# DM1098LUXD-LITE_IMX214.net
KiCad netlist of a schematic drawn in Altium Designer
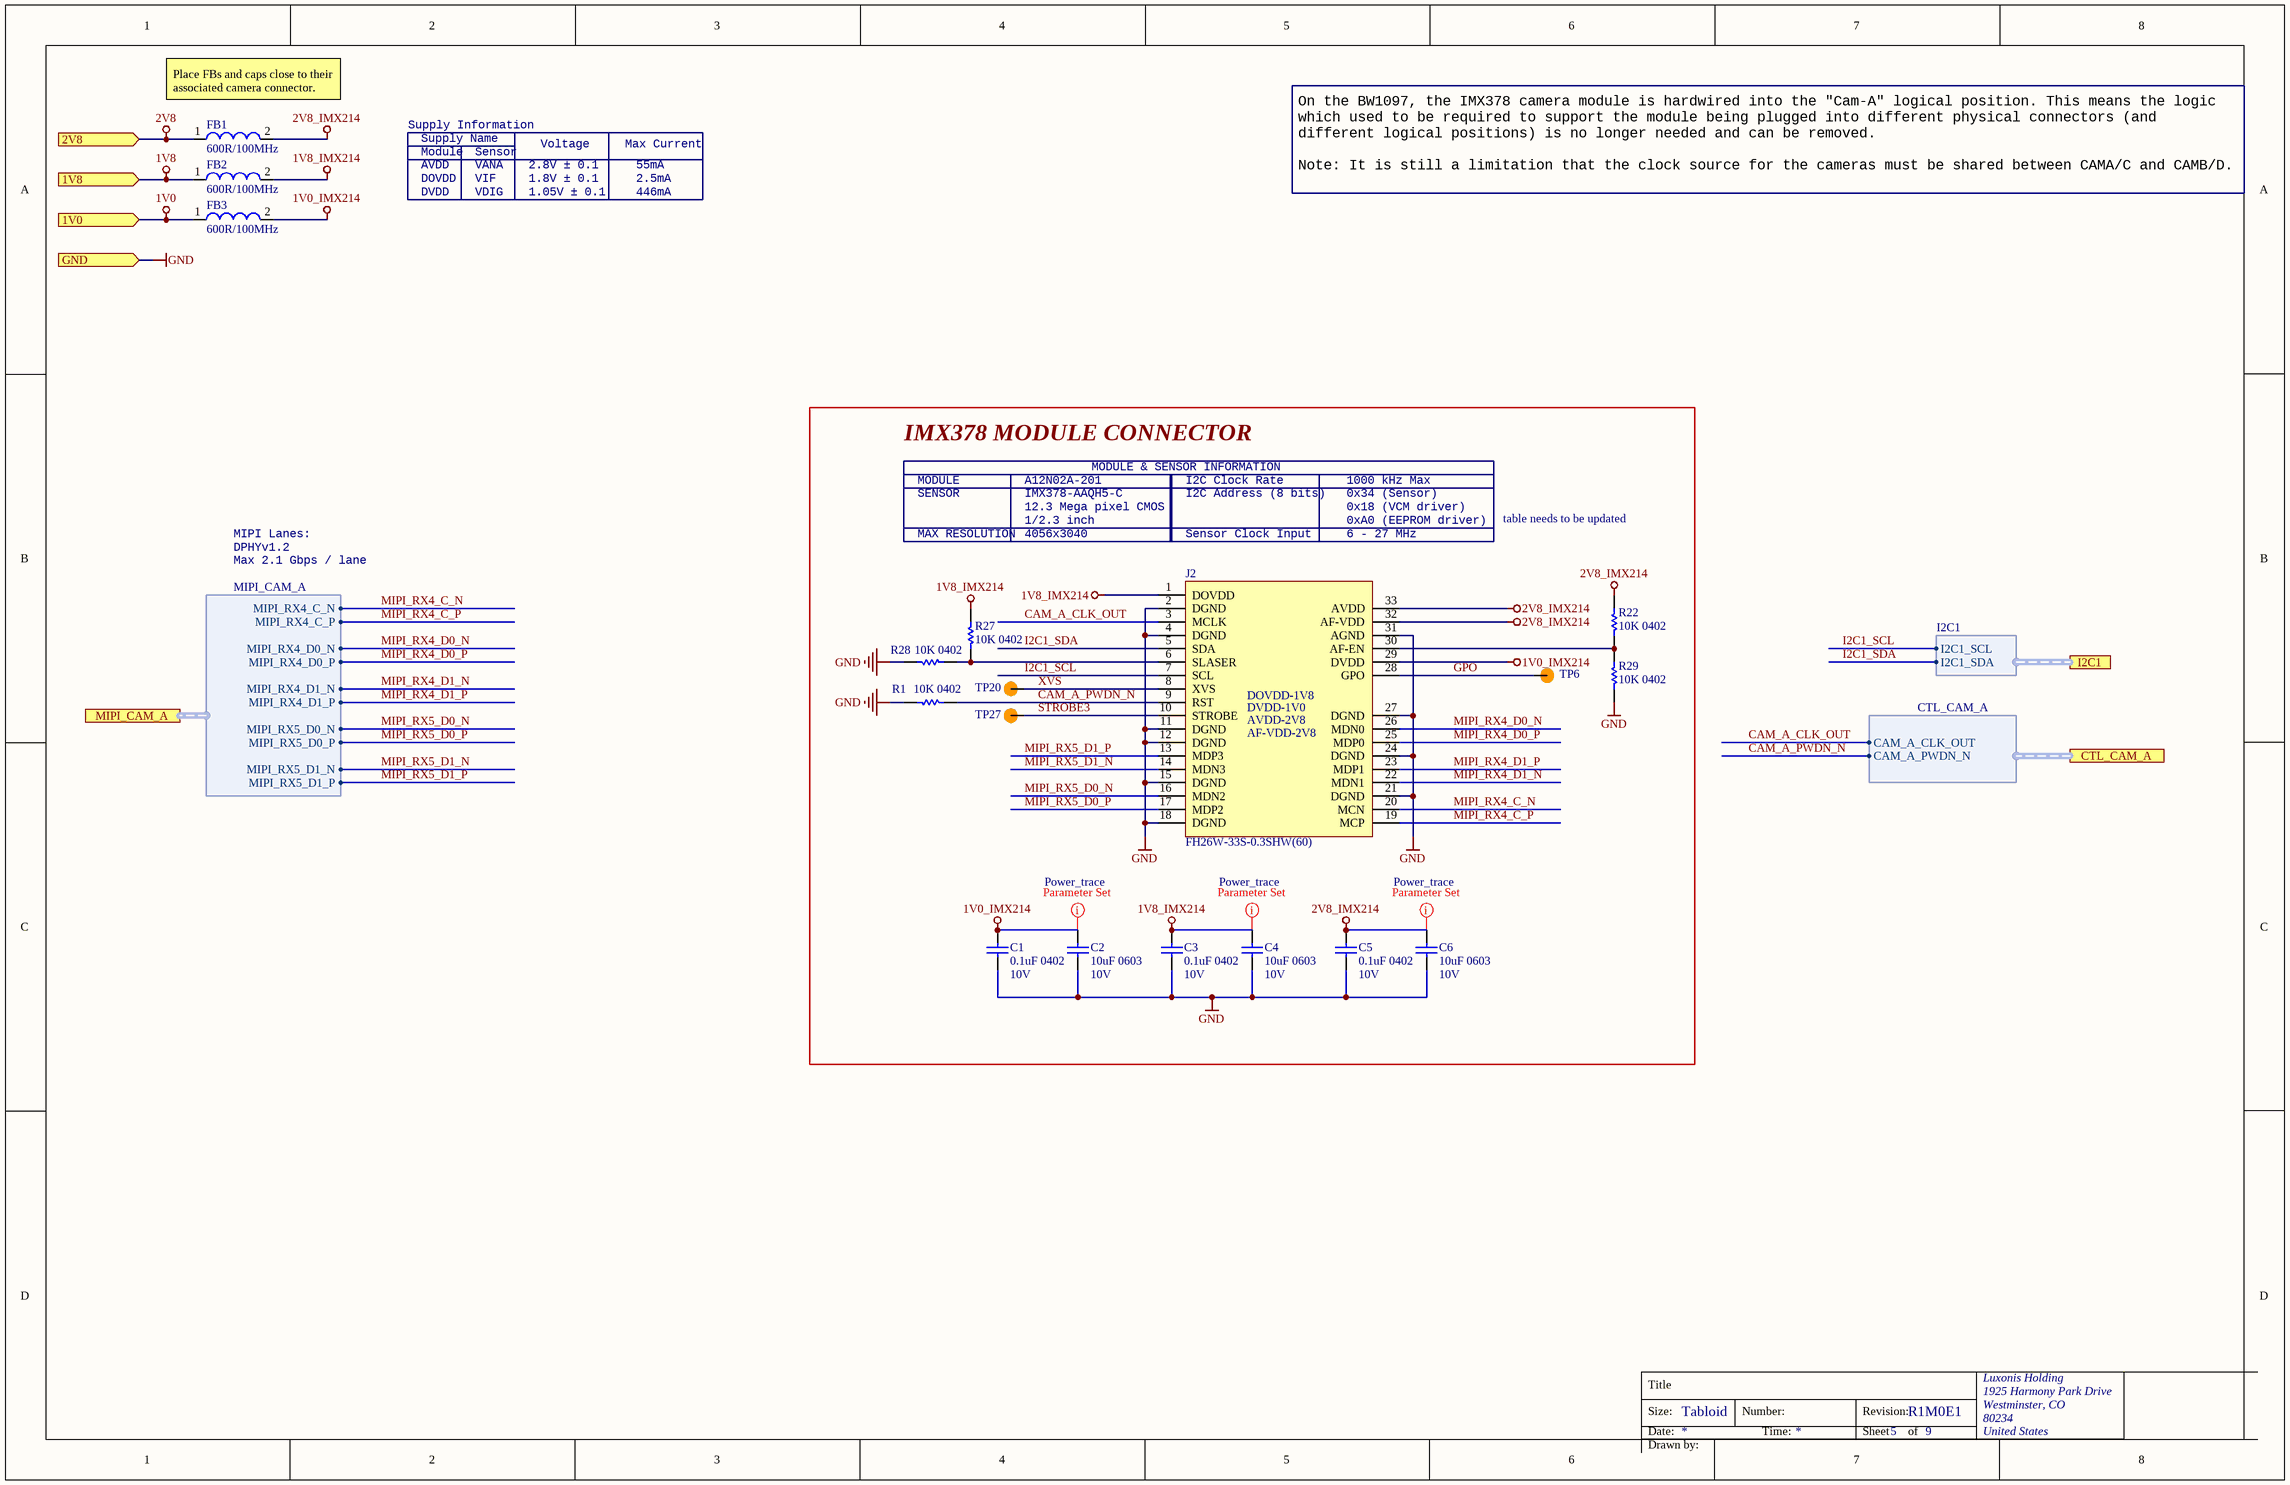
[diagram p0: DM1098LUXD-LITE_IMX214.SchDoc]

(export (version "E")
  (design (tool "Eeschema 10.0.6"))
  (components
    (comp (ref "C1")
      (value "0.1uF 0402")
      (footprint "CAP_Altium_Vault_Generic:CAPC0402(1005)70_L")
      (description "CAP CER 0.1UF 10V X7R 0402 5%")
      (fields (field (name "TOLERANCE") "5%") (field (name "VOLTAGE RATING") "10V"))
      (libsource (lib "LuxonisMaster") (part "GRM155R71A104JA01D"))
    )
    (comp (ref "C2")
      (value "10uF 0603")
      (footprint "CAP_Altium_Vault_Generic:CAPC0603(1608)100_L")
      (description "CAP CER 10UF 10V X5R 0603 20%")
      (fields (field (name "TOLERANCE") "20%") (field (name "VOLTAGE RATING") "10V"))
      (libsource (lib "LuxonisMaster") (part "GRM188R61A106ME69D"))
    )
    (comp (ref "C3")
      (value "0.1uF 0402")
      (footprint "CAP_Altium_Vault_Generic:CAPC0402(1005)70_L")
      (description "CAP CER 0.1UF 10V X7R 0402 5%")
      (fields (field (name "TOLERANCE") "5%") (field (name "VOLTAGE RATING") "10V"))
      (libsource (lib "LuxonisMaster") (part "GRM155R71A104JA01D"))
    )
    (comp (ref "C4")
      (value "10uF 0603")
      (footprint "CAP_Altium_Vault_Generic:CAPC0603(1608)100_L")
      (description "CAP CER 10UF 10V X5R 0603 20%")
      (fields (field (name "TOLERANCE") "20%") (field (name "VOLTAGE RATING") "10V"))
      (libsource (lib "LuxonisMaster") (part "GRM188R61A106ME69D"))
    )
    (comp (ref "C5")
      (value "0.1uF 0402")
      (footprint "CAP_Altium_Vault_Generic:CAPC0402(1005)70_L")
      (description "CAP CER 0.1UF 10V X7R 0402 5%")
      (fields (field (name "TOLERANCE") "5%") (field (name "VOLTAGE RATING") "10V"))
      (libsource (lib "LuxonisMaster") (part "GRM155R71A104JA01D"))
    )
    (comp (ref "C6")
      (value "10uF 0603")
      (footprint "CAP_Altium_Vault_Generic:CAPC0603(1608)100_L")
      (description "CAP CER 10UF 10V X5R 0603 20%")
      (fields (field (name "TOLERANCE") "20%") (field (name "VOLTAGE RATING") "10V"))
      (libsource (lib "LuxonisMaster") (part "GRM188R61A106ME69D"))
    )
    (comp (ref "FB1")
      (value "600R/100MHz")
      (footprint "LuxonisMaster:2508056017Y2")
      (description "FERRITE BEAD, 0.1OHM, 2A, 0805, 600R/100MHz")
      (fields (field (name "TOLERANCE") "25%"))
      (libsource (lib "LuxonisMaster") (part "2508056017Y2"))
    )
    (comp (ref "FB2")
      (value "600R/100MHz")
      (footprint "LuxonisMaster:2508056017Y2")
      (description "FERRITE BEAD, 0.1OHM, 2A, 0805, 600R/100MHz")
      (fields (field (name "TOLERANCE") "25%"))
      (libsource (lib "LuxonisMaster") (part "2508056017Y2"))
    )
    (comp (ref "FB3")
      (value "600R/100MHz")
      (footprint "LuxonisMaster:2508056017Y2")
      (description "FERRITE BEAD, 0.1OHM, 2A, 0805, 600R/100MHz")
      (fields (field (name "TOLERANCE") "25%"))
      (libsource (lib "LuxonisMaster") (part "2508056017Y2"))
    )
    (comp (ref "J2")
      (value "FH26W-33S-0.3SHW(60)")
      (footprint "ACIMX-214")
      (description "FFC/FPC Connector, 33 Contact(s), 1 Row(s), Female, Right Angle, Surface Mount Terminal")
      (libsource (lib "DM1098LUXD-LITE") (part "AC-IMX214_Connector"))
    )
    (comp (ref "R1")
      (value "10K 0402")
      (footprint "RES_Altium_Vault_Generic:RESC0402(1005)_L")
      (fields (field (name "TOLERANCE") "1%"))
      (libsource (lib "LuxonisMaster") (part "RC0402FR-1310KL"))
    )
    (comp (ref "R22")
      (value "10K 0402")
      (footprint "RES_Altium_Vault_Generic:RESC0402(1005)_L")
      (fields (field (name "TOLERANCE") "1%"))
      (libsource (lib "LuxonisMaster") (part "RC0402FR-1310KL"))
    )
    (comp (ref "R27")
      (value "10K 0402")
      (footprint "RES_Altium_Vault_Generic:RESC0402(1005)_L")
      (fields (field (name "TOLERANCE") "1%"))
      (libsource (lib "LuxonisMaster") (part "RC0402FR-1310KL"))
    )
    (comp (ref "R28")
      (value "10K 0402")
      (footprint "RES_Altium_Vault_Generic:RESC0402(1005)_L")
      (fields (field (name "TOLERANCE") "1%"))
      (libsource (lib "LuxonisMaster") (part "RC0402FR-1310KL"))
    )
    (comp (ref "R29")
      (value "10K 0402")
      (footprint "RES_Altium_Vault_Generic:RESC0402(1005)_L")
      (fields (field (name "TOLERANCE") "1%"))
      (libsource (lib "LuxonisMaster") (part "RC0402FR-1310KL"))
    )
    (comp (ref "TP6")
      (value "TP100_200_NS")
      (footprint "LuxonisMaster:TP100_200_NS")
      (libsource (lib "LuxonisMaster") (part "TEST_POINT"))
    )
    (comp (ref "TP20")
      (value "TP100_200_NS")
      (footprint "LuxonisMaster:TP100_200_NS")
      (libsource (lib "LuxonisMaster") (part "TEST_POINT"))
    )
    (comp (ref "TP27")
      (value "TP100_200_NS")
      (footprint "LuxonisMaster:TP100_200_NS")
      (libsource (lib "LuxonisMaster") (part "TEST_POINT"))
    )
  )
  (nets
    (net (code "4") (name "/CAM_A_CLK_OUT") (class "Default")
      (node (ref "J2") (pin "3") (pinfunction "MCLK_3") (pintype "passive"))
    )
    (net (code "5") (name "/CAM_A_PWDN_N") (class "Default")
      (node (ref "J2") (pin "9") (pinfunction "RST_9") (pintype "passive"))
      (node (ref "R1") (pin "1") (pinfunction "1_1") (pintype "passive"))
    )
    (net (code "6") (name "/GPO") (class "Default")
      (node (ref "J2") (pin "28") (pinfunction "GPO_28") (pintype "passive"))
      (node (ref "TP6") (pin "1") (pintype "passive"))
    )
    (net (code "7") (name "/I2C1_SCL") (class "Default")
      (node (ref "J2") (pin "7") (pinfunction "SCL_7") (pintype "passive"))
    )
    (net (code "8") (name "/I2C1_SDA") (class "Default")
      (node (ref "J2") (pin "5") (pinfunction "SDA_5") (pintype "passive"))
    )
    (net (code "9") (name "/MIPI_RX4_C_N") (class "Default")
      (node (ref "J2") (pin "20") (pinfunction "MCN_20") (pintype "passive"))
    )
    (net (code "10") (name "/MIPI_RX4_C_P") (class "Default")
      (node (ref "J2") (pin "19") (pinfunction "MCP_19") (pintype "passive"))
    )
    (net (code "11") (name "/MIPI_RX4_D0_N") (class "Default")
      (node (ref "J2") (pin "26") (pinfunction "MDN0_26") (pintype "passive"))
    )
    (net (code "12") (name "/MIPI_RX4_D0_P") (class "Default")
      (node (ref "J2") (pin "25") (pinfunction "MDP0_25") (pintype "passive"))
    )
    (net (code "13") (name "/MIPI_RX4_D1_N") (class "Default")
      (node (ref "J2") (pin "22") (pinfunction "MDN1_22") (pintype "passive"))
    )
    (net (code "14") (name "/MIPI_RX4_D1_P") (class "Default")
      (node (ref "J2") (pin "23") (pinfunction "MDP1_23") (pintype "passive"))
    )
    (net (code "15") (name "/MIPI_RX5_D0_N") (class "Default")
      (node (ref "J2") (pin "16") (pinfunction "MDN2_16") (pintype "passive"))
    )
    (net (code "16") (name "/MIPI_RX5_D0_P") (class "Default")
      (node (ref "J2") (pin "17") (pinfunction "MDP2_17") (pintype "passive"))
    )
    (net (code "17") (name "/MIPI_RX5_D1_N") (class "Default")
      (node (ref "J2") (pin "14") (pinfunction "MDN3_14") (pintype "passive"))
    )
    (net (code "18") (name "/MIPI_RX5_D1_P") (class "Default")
      (node (ref "J2") (pin "13") (pinfunction "MDP3_13") (pintype "passive"))
    )
    (net (code "19") (name "/STROBE3") (class "Default")
      (node (ref "J2") (pin "10") (pinfunction "STROBE_10") (pintype "passive"))
      (node (ref "TP27") (pin "1") (pintype "passive"))
    )
    (net (code "20") (name "/XVS") (class "Default")
      (node (ref "J2") (pin "8") (pinfunction "XVS_8") (pintype "passive"))
      (node (ref "TP20") (pin "1") (pintype "passive"))
    )
    (net (code "24") (name "1V0") (class "Default")
      (node (ref "FB3") (pin "1") (pinfunction "1_1") (pintype "passive"))
    )
    (net (code "25") (name "1V0_IMX214") (class "Default")
      (node (ref "C1") (pin "2") (pinfunction "2_2") (pintype "passive"))
      (node (ref "C2") (pin "2") (pinfunction "2_2") (pintype "passive"))
      (node (ref "FB3") (pin "2") (pinfunction "2_2") (pintype "passive"))
      (node (ref "J2") (pin "29") (pinfunction "DVDD_29") (pintype "passive"))
    )
    (net (code "26") (name "1V8") (class "Default")
      (node (ref "FB2") (pin "1") (pinfunction "1_1") (pintype "passive"))
    )
    (net (code "27") (name "1V8_IMX214") (class "Default")
      (node (ref "C3") (pin "2") (pinfunction "2_2") (pintype "passive"))
      (node (ref "C4") (pin "2") (pinfunction "2_2") (pintype "passive"))
      (node (ref "FB2") (pin "2") (pinfunction "2_2") (pintype "passive"))
      (node (ref "J2") (pin "1") (pinfunction "DOVDD_1") (pintype "passive"))
      (node (ref "R27") (pin "2") (pinfunction "2_2") (pintype "passive"))
    )
    (net (code "28") (name "2V8") (class "Default")
      (node (ref "FB1") (pin "1") (pinfunction "1_1") (pintype "passive"))
    )
    (net (code "29") (name "2V8_IMX214") (class "Default")
      (node (ref "C5") (pin "2") (pinfunction "2_2") (pintype "passive"))
      (node (ref "C6") (pin "2") (pinfunction "2_2") (pintype "passive"))
      (node (ref "FB1") (pin "2") (pinfunction "2_2") (pintype "passive"))
      (node (ref "J2") (pin "32") (pinfunction "AF-VDD_32") (pintype "passive"))
      (node (ref "J2") (pin "33") (pinfunction "AVDD_33") (pintype "passive"))
      (node (ref "R22") (pin "1") (pinfunction "1_1") (pintype "passive"))
    )
    (net (code "30") (name "GND") (class "Default")
      (node (ref "C1") (pin "1") (pinfunction "1_1") (pintype "passive"))
      (node (ref "C2") (pin "1") (pinfunction "1_1") (pintype "passive"))
      (node (ref "C3") (pin "1") (pinfunction "1_1") (pintype "passive"))
      (node (ref "C4") (pin "1") (pinfunction "1_1") (pintype "passive"))
      (node (ref "C5") (pin "1") (pinfunction "1_1") (pintype "passive"))
      (node (ref "C6") (pin "1") (pinfunction "1_1") (pintype "passive"))
      (node (ref "J2") (pin "11") (pinfunction "DGND_11") (pintype "passive"))
      (node (ref "J2") (pin "12") (pinfunction "DGND_12") (pintype "passive"))
      (node (ref "J2") (pin "15") (pinfunction "DGND_15") (pintype "passive"))
      (node (ref "J2") (pin "18") (pinfunction "DGND_18") (pintype "passive"))
      (node (ref "J2") (pin "2") (pinfunction "DGND_2") (pintype "passive"))
      (node (ref "J2") (pin "21") (pinfunction "DGND_21") (pintype "passive"))
      (node (ref "J2") (pin "24") (pinfunction "DGND_24") (pintype "passive"))
      (node (ref "J2") (pin "27") (pinfunction "DGND_27") (pintype "passive"))
      (node (ref "J2") (pin "31") (pinfunction "AGND_31") (pintype "passive"))
      (node (ref "J2") (pin "4") (pinfunction "DGND_4") (pintype "passive"))
      (node (ref "R1") (pin "2") (pinfunction "2_2") (pintype "passive"))
      (node (ref "R28") (pin "2") (pinfunction "2_2") (pintype "passive"))
      (node (ref "R29") (pin "2") (pinfunction "2_2") (pintype "passive"))
    )
    (net (code "31") (name "Net-(J2-AF-EN)") (class "Default")
      (node (ref "J2") (pin "30") (pinfunction "AF-EN_30") (pintype "passive"))
      (node (ref "R22") (pin "2") (pinfunction "2_2") (pintype "passive"))
      (node (ref "R29") (pin "1") (pinfunction "1_1") (pintype "passive"))
    )
    (net (code "32") (name "Net-(J2-SLASER)") (class "Default")
      (node (ref "J2") (pin "6") (pinfunction "SLASER_6") (pintype "passive"))
      (node (ref "R27") (pin "1") (pinfunction "1_1") (pintype "passive"))
      (node (ref "R28") (pin "1") (pinfunction "1_1") (pintype "passive"))
    )
  )
)
